# Clock_management.net
KiCad netlist of a schematic drawn in Altium Designer
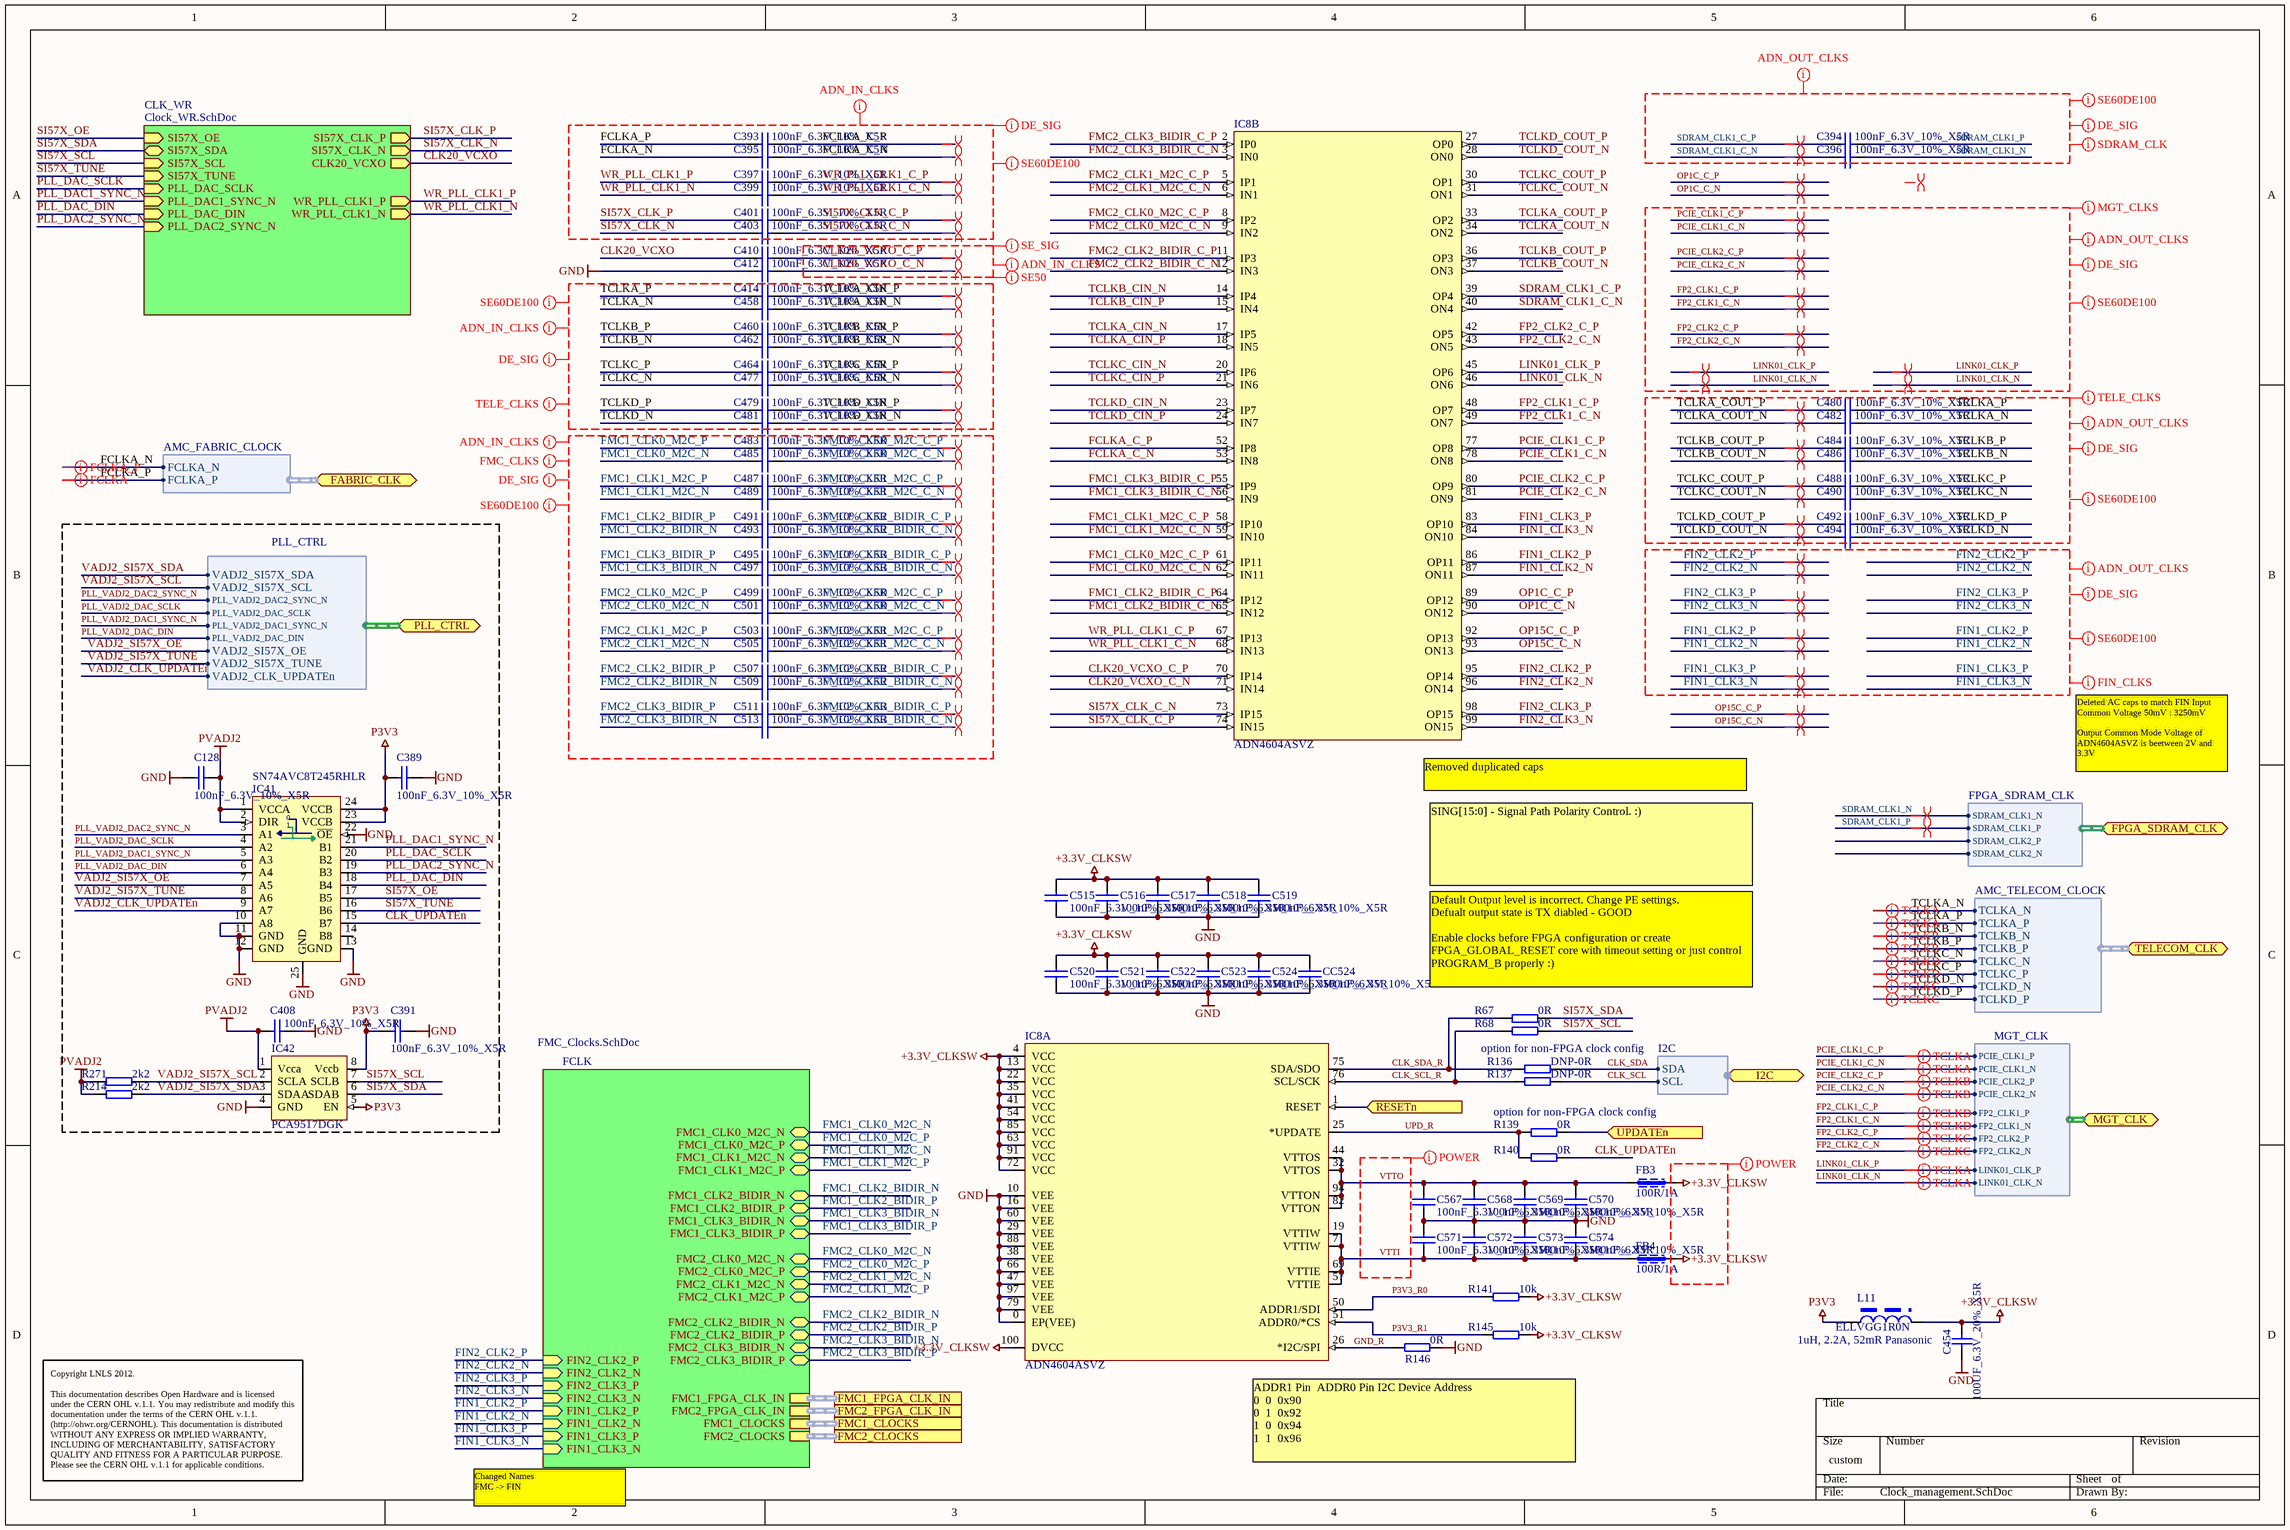
[diagram p0: Clock_management.SchDoc]

(export (version "E")
  (design (tool "Eeschema 10.0.6"))
  (components
    (comp (ref "C128")
      (value "100nF_6.3V_10%_X5R")
      (footprint "0201C")
      (description "Capacitor SMD")
      (libsource (lib "LIBRARY_SCH") (part "CAP_SMD_0201"))
    )
    (comp (ref "C389")
      (value "100nF_6.3V_10%_X5R")
      (footprint "0201C")
      (description "Capacitor SMD")
      (libsource (lib "LIBRARY_SCH") (part "CAP_SMD_0201"))
    )
    (comp (ref "C391")
      (value "100nF_6.3V_10%_X5R")
      (footprint "0201C")
      (description "Capacitor SMD")
      (libsource (lib "LIBRARY_SCH") (part "CAP_SMD_0201"))
    )
    (comp (ref "C393")
      (value "100nF_6.3V_10%_X5R")
      (footprint "0201C")
      (description "Capacitor SMD")
      (libsource (lib "LIBRARY_SCH") (part "CAP_SMD_0201"))
    )
    (comp (ref "C394")
      (value "100nF_6.3V_10%_X5R")
      (footprint "0201C")
      (description "Capacitor SMD")
      (libsource (lib "LIBRARY_SCH") (part "CAP_SMD_0201"))
    )
    (comp (ref "C395")
      (value "100nF_6.3V_10%_X5R")
      (footprint "0201C")
      (description "Capacitor SMD")
      (libsource (lib "LIBRARY_SCH") (part "CAP_SMD_0201"))
    )
    (comp (ref "C396")
      (value "100nF_6.3V_10%_X5R")
      (footprint "0201C")
      (description "Capacitor SMD")
      (libsource (lib "LIBRARY_SCH") (part "CAP_SMD_0201"))
    )
    (comp (ref "C397")
      (value "100nF_6.3V_10%_X5R")
      (footprint "0201C")
      (description "Capacitor SMD")
      (libsource (lib "LIBRARY_SCH") (part "CAP_SMD_0201"))
    )
    (comp (ref "C399")
      (value "100nF_6.3V_10%_X5R")
      (footprint "0201C")
      (description "Capacitor SMD")
      (libsource (lib "LIBRARY_SCH") (part "CAP_SMD_0201"))
    )
    (comp (ref "C401")
      (value "100nF_6.3V_10%_X5R")
      (footprint "0201C")
      (description "Capacitor SMD")
      (libsource (lib "LIBRARY_SCH") (part "CAP_SMD_0201"))
    )
    (comp (ref "C403")
      (value "100nF_6.3V_10%_X5R")
      (footprint "0201C")
      (description "Capacitor SMD")
      (libsource (lib "LIBRARY_SCH") (part "CAP_SMD_0201"))
    )
    (comp (ref "C408")
      (value "100nF_6.3V_10%_X5R")
      (footprint "0201C")
      (description "Capacitor SMD")
      (libsource (lib "LIBRARY_SCH") (part "CAP_SMD_0201"))
    )
    (comp (ref "C410")
      (value "100nF_6.3V_10%_X5R")
      (footprint "0201C")
      (description "Capacitor SMD")
      (libsource (lib "LIBRARY_SCH") (part "CAP_SMD_0201"))
    )
    (comp (ref "C412")
      (value "100nF_6.3V_10%_X5R")
      (footprint "0201C")
      (description "Capacitor SMD")
      (libsource (lib "LIBRARY_SCH") (part "CAP_SMD_0201"))
    )
    (comp (ref "C414")
      (value "100nF_6.3V_10%_X5R")
      (footprint "0201C")
      (description "Capacitor SMD")
      (libsource (lib "LIBRARY_SCH") (part "CAP_SMD_0201"))
    )
    (comp (ref "C454")
      (value "100UF_6.3V_20%_X5R")
      (footprint "CAPC3225X270N")
      (description "Non-polarised capacitor")
      (fields
        (field (name "PART NUMBER") "CC1210_100UF_6.3V_20%_X5R")
        (field (name "VOLTAGE") "6.3V")
        (field (name "AUTHOR") "CERN DEM JLC")
      )
      (libsource (lib "Capacitors") (part "Capacitor - non polarized"))
    )
    (comp (ref "C458")
      (value "100nF_6.3V_10%_X5R")
      (footprint "0201C")
      (description "Capacitor SMD")
      (libsource (lib "LIBRARY_SCH") (part "CAP_SMD_0201"))
    )
    (comp (ref "C460")
      (value "100nF_6.3V_10%_X5R")
      (footprint "0201C")
      (description "Capacitor SMD")
      (libsource (lib "LIBRARY_SCH") (part "CAP_SMD_0201"))
    )
    (comp (ref "C462")
      (value "100nF_6.3V_10%_X5R")
      (footprint "0201C")
      (description "Capacitor SMD")
      (libsource (lib "LIBRARY_SCH") (part "CAP_SMD_0201"))
    )
    (comp (ref "C464")
      (value "100nF_6.3V_10%_X5R")
      (footprint "0201C")
      (description "Capacitor SMD")
      (libsource (lib "LIBRARY_SCH") (part "CAP_SMD_0201"))
    )
    (comp (ref "C477")
      (value "100nF_6.3V_10%_X5R")
      (footprint "0201C")
      (description "Capacitor SMD")
      (libsource (lib "LIBRARY_SCH") (part "CAP_SMD_0201"))
    )
    (comp (ref "C479")
      (value "100nF_6.3V_10%_X5R")
      (footprint "0201C")
      (description "Capacitor SMD")
      (libsource (lib "LIBRARY_SCH") (part "CAP_SMD_0201"))
    )
    (comp (ref "C480")
      (value "100nF_6.3V_10%_X5R")
      (footprint "0201C")
      (description "Capacitor SMD")
      (libsource (lib "LIBRARY_SCH") (part "CAP_SMD_0201"))
    )
    (comp (ref "C481")
      (value "100nF_6.3V_10%_X5R")
      (footprint "0201C")
      (description "Capacitor SMD")
      (libsource (lib "LIBRARY_SCH") (part "CAP_SMD_0201"))
    )
    (comp (ref "C482")
      (value "100nF_6.3V_10%_X5R")
      (footprint "0201C")
      (description "Capacitor SMD")
      (libsource (lib "LIBRARY_SCH") (part "CAP_SMD_0201"))
    )
    (comp (ref "C483")
      (value "100nF_6.3V_10%_X5R")
      (footprint "0201C")
      (description "Capacitor SMD")
      (libsource (lib "LIBRARY_SCH") (part "CAP_SMD_0201"))
    )
    (comp (ref "C484")
      (value "100nF_6.3V_10%_X5R")
      (footprint "0201C")
      (description "Capacitor SMD")
      (libsource (lib "LIBRARY_SCH") (part "CAP_SMD_0201"))
    )
    (comp (ref "C485")
      (value "100nF_6.3V_10%_X5R")
      (footprint "0201C")
      (description "Capacitor SMD")
      (libsource (lib "LIBRARY_SCH") (part "CAP_SMD_0201"))
    )
    (comp (ref "C486")
      (value "100nF_6.3V_10%_X5R")
      (footprint "0201C")
      (description "Capacitor SMD")
      (libsource (lib "LIBRARY_SCH") (part "CAP_SMD_0201"))
    )
    (comp (ref "C487")
      (value "100nF_6.3V_10%_X5R")
      (footprint "0201C")
      (description "Capacitor SMD")
      (libsource (lib "LIBRARY_SCH") (part "CAP_SMD_0201"))
    )
    (comp (ref "C488")
      (value "100nF_6.3V_10%_X5R")
      (footprint "0201C")
      (description "Capacitor SMD")
      (libsource (lib "LIBRARY_SCH") (part "CAP_SMD_0201"))
    )
    (comp (ref "C489")
      (value "100nF_6.3V_10%_X5R")
      (footprint "0201C")
      (description "Capacitor SMD")
      (libsource (lib "LIBRARY_SCH") (part "CAP_SMD_0201"))
    )
    (comp (ref "C490")
      (value "100nF_6.3V_10%_X5R")
      (footprint "0201C")
      (description "Capacitor SMD")
      (libsource (lib "LIBRARY_SCH") (part "CAP_SMD_0201"))
    )
    (comp (ref "C491")
      (value "100nF_6.3V_10%_X5R")
      (footprint "0201C")
      (description "Capacitor SMD")
      (libsource (lib "LIBRARY_SCH") (part "CAP_SMD_0201"))
    )
    (comp (ref "C492")
      (value "100nF_6.3V_10%_X5R")
      (footprint "0201C")
      (description "Capacitor SMD")
      (libsource (lib "LIBRARY_SCH") (part "CAP_SMD_0201"))
    )
    (comp (ref "C493")
      (value "100nF_6.3V_10%_X5R")
      (footprint "0201C")
      (description "Capacitor SMD")
      (libsource (lib "LIBRARY_SCH") (part "CAP_SMD_0201"))
    )
    (comp (ref "C494")
      (value "100nF_6.3V_10%_X5R")
      (footprint "0201C")
      (description "Capacitor SMD")
      (libsource (lib "LIBRARY_SCH") (part "CAP_SMD_0201"))
    )
    (comp (ref "C495")
      (value "100nF_6.3V_10%_X5R")
      (footprint "0201C")
      (description "Capacitor SMD")
      (libsource (lib "LIBRARY_SCH") (part "CAP_SMD_0201"))
    )
    (comp (ref "C497")
      (value "100nF_6.3V_10%_X5R")
      (footprint "0201C")
      (description "Capacitor SMD")
      (libsource (lib "LIBRARY_SCH") (part "CAP_SMD_0201"))
    )
    (comp (ref "C499")
      (value "100nF_6.3V_10%_X5R")
      (footprint "0201C")
      (description "Capacitor SMD")
      (libsource (lib "LIBRARY_SCH") (part "CAP_SMD_0201"))
    )
    (comp (ref "C501")
      (value "100nF_6.3V_10%_X5R")
      (footprint "0201C")
      (description "Capacitor SMD")
      (libsource (lib "LIBRARY_SCH") (part "CAP_SMD_0201"))
    )
    (comp (ref "C503")
      (value "100nF_6.3V_10%_X5R")
      (footprint "0201C")
      (description "Capacitor SMD")
      (libsource (lib "LIBRARY_SCH") (part "CAP_SMD_0201"))
    )
    (comp (ref "C505")
      (value "100nF_6.3V_10%_X5R")
      (footprint "0201C")
      (description "Capacitor SMD")
      (libsource (lib "LIBRARY_SCH") (part "CAP_SMD_0201"))
    )
    (comp (ref "C507")
      (value "100nF_6.3V_10%_X5R")
      (footprint "0201C")
      (description "Capacitor SMD")
      (libsource (lib "LIBRARY_SCH") (part "CAP_SMD_0201"))
    )
    (comp (ref "C509")
      (value "100nF_6.3V_10%_X5R")
      (footprint "0201C")
      (description "Capacitor SMD")
      (libsource (lib "LIBRARY_SCH") (part "CAP_SMD_0201"))
    )
    (comp (ref "C511")
      (value "100nF_6.3V_10%_X5R")
      (footprint "0201C")
      (description "Capacitor SMD")
      (libsource (lib "LIBRARY_SCH") (part "CAP_SMD_0201"))
    )
    (comp (ref "C513")
      (value "100nF_6.3V_10%_X5R")
      (footprint "0201C")
      (description "Capacitor SMD")
      (libsource (lib "LIBRARY_SCH") (part "CAP_SMD_0201"))
    )
    (comp (ref "C515")
      (value "100nF_6.3V_10%_X5R")
      (footprint "0201C")
      (description "Capacitor SMD")
      (libsource (lib "LIBRARY_SCH") (part "CAP_SMD_0201"))
    )
    (comp (ref "C516")
      (value "100nF_6.3V_10%_X5R")
      (footprint "0201C")
      (description "Capacitor SMD")
      (libsource (lib "LIBRARY_SCH") (part "CAP_SMD_0201"))
    )
    (comp (ref "C517")
      (value "100nF_6.3V_10%_X5R")
      (footprint "0201C")
      (description "Capacitor SMD")
      (libsource (lib "LIBRARY_SCH") (part "CAP_SMD_0201"))
    )
    (comp (ref "C518")
      (value "100nF_6.3V_10%_X5R")
      (footprint "0201C")
      (description "Capacitor SMD")
      (libsource (lib "LIBRARY_SCH") (part "CAP_SMD_0201"))
    )
    (comp (ref "C519")
      (value "100nF_6.3V_10%_X5R")
      (footprint "0201C")
      (description "Capacitor SMD")
      (libsource (lib "LIBRARY_SCH") (part "CAP_SMD_0201"))
    )
    (comp (ref "C520")
      (value "100nF_6.3V_10%_X5R")
      (footprint "0201C")
      (description "Capacitor SMD")
      (libsource (lib "LIBRARY_SCH") (part "CAP_SMD_0201"))
    )
    (comp (ref "C521")
      (value "100nF_6.3V_10%_X5R")
      (footprint "0201C")
      (description "Capacitor SMD")
      (libsource (lib "LIBRARY_SCH") (part "CAP_SMD_0201"))
    )
    (comp (ref "C522")
      (value "100nF_6.3V_10%_X5R")
      (footprint "0201C")
      (description "Capacitor SMD")
      (libsource (lib "LIBRARY_SCH") (part "CAP_SMD_0201"))
    )
    (comp (ref "C523")
      (value "100nF_6.3V_10%_X5R")
      (footprint "0201C")
      (description "Capacitor SMD")
      (libsource (lib "LIBRARY_SCH") (part "CAP_SMD_0201"))
    )
    (comp (ref "C524")
      (value "100nF_6.3V_10%_X5R")
      (footprint "0201C")
      (description "Capacitor SMD")
      (libsource (lib "LIBRARY_SCH") (part "CAP_SMD_0201"))
    )
    (comp (ref "C567")
      (value "100nF_6.3V_10%_X5R")
      (footprint "0201C")
      (description "Capacitor SMD")
      (libsource (lib "LIBRARY_SCH") (part "CAP_SMD_0201"))
    )
    (comp (ref "C568")
      (value "100nF_6.3V_10%_X5R")
      (footprint "0201C")
      (description "Capacitor SMD")
      (libsource (lib "LIBRARY_SCH") (part "CAP_SMD_0201"))
    )
    (comp (ref "C569")
      (value "100nF_6.3V_10%_X5R")
      (footprint "0201C")
      (description "Capacitor SMD")
      (libsource (lib "LIBRARY_SCH") (part "CAP_SMD_0201"))
    )
    (comp (ref "C570")
      (value "100nF_6.3V_10%_X5R")
      (footprint "0201C")
      (description "Capacitor SMD")
      (libsource (lib "LIBRARY_SCH") (part "CAP_SMD_0201"))
    )
    (comp (ref "C571")
      (value "100nF_6.3V_10%_X5R")
      (footprint "0201C")
      (description "Capacitor SMD")
      (libsource (lib "LIBRARY_SCH") (part "CAP_SMD_0201"))
    )
    (comp (ref "C572")
      (value "100nF_6.3V_10%_X5R")
      (footprint "0201C")
      (description "Capacitor SMD")
      (libsource (lib "LIBRARY_SCH") (part "CAP_SMD_0201"))
    )
    (comp (ref "C573")
      (value "100nF_6.3V_10%_X5R")
      (footprint "0201C")
      (description "Capacitor SMD")
      (libsource (lib "LIBRARY_SCH") (part "CAP_SMD_0201"))
    )
    (comp (ref "C574")
      (value "100nF_6.3V_10%_X5R")
      (footprint "0201C")
      (description "Capacitor SMD")
      (libsource (lib "LIBRARY_SCH") (part "CAP_SMD_0201"))
    )
    (comp (ref "CC524")
      (value "100nF_6.3V_10%_X5R")
      (footprint "0201C")
      (description "Capacitor SMD")
      (libsource (lib "LIBRARY_SCH") (part "CAP_SMD_0201"))
    )
    (comp (ref "FB3")
      (value "100R/1A")
      (footprint "0603L")
      (description "ferrite bead 100R@100MHz 1A")
      (libsource (lib "LIBRARY_SCH") (part "L_FERRITE_BEAD_0603"))
    )
    (comp (ref "FB4")
      (value "100R/1A")
      (footprint "0603L")
      (description "ferrite bead 100R@100MHz 1A")
      (libsource (lib "LIBRARY_SCH") (part "L_FERRITE_BEAD_0603"))
    )
    (comp (ref "IC8")
      (value "ADN4604ASVZ")
      (footprint "TQFP100_TP")
      (description "16x16 CML crosspoint switch")
      (libsource (lib "LIBRARY_SCH") (part "IFC_ADN4604ASVZ"))
    )
    (comp (ref "IC41")
      (value "SN74AVC8T245RHLR")
      (footprint "QFN50P350X550X100-24N")
      (description "8 channel bidir translator buffer (1.4..3.6V)")
      (libsource (lib "LIBRARY_SCH") (part "74AVC8T245_QFN"))
    )
    (comp (ref "IC42")
      (value "PCA9517DGK")
      (footprint "msop-8")
      (description "LEVEL-TRANSLATING I2C BUS REPEATER")
      (libsource (lib "LIBRARY_SCH") (part "IFC_PCA9517"))
    )
    (comp (ref "L11")
      (value "ELLVGG1R0N")
      (footprint "L_ELLVGG2R2N")
      (description "2.2uH, 1.4A, 92mR Panasonic")
      (fields (field (name "ALTIUM_UNNAMED_1") "1uH, 2.2A, 52mR Panasonic"))
      (libsource (lib "LIBRARY_SCH") (part "L_CHOKE_ELLVGG"))
    )
    (comp (ref "R67")
      (value "0R")
      (footprint "0402R")
      (description "SMD Resistor")
      (libsource (lib "LIBRARY_SCH") (part "RES_0402"))
    )
    (comp (ref "R68")
      (value "0R")
      (footprint "0402R")
      (description "SMD Resistor")
      (libsource (lib "LIBRARY_SCH") (part "RES_0402"))
    )
    (comp (ref "R136")
      (value "DNP-0R")
      (footprint "0402R")
      (description "SMD Resistor")
      (libsource (lib "LIBRARY_SCH") (part "RES_0402"))
    )
    (comp (ref "R137")
      (value "DNP-0R")
      (footprint "0402R")
      (description "SMD Resistor")
      (libsource (lib "LIBRARY_SCH") (part "RES_0402"))
    )
    (comp (ref "R139")
      (value "0R")
      (footprint "0402R")
      (description "SMD Resistor")
      (libsource (lib "LIBRARY_SCH") (part "RES_0402"))
    )
    (comp (ref "R140")
      (value "0R")
      (footprint "0402R")
      (description "SMD Resistor")
      (libsource (lib "LIBRARY_SCH") (part "RES_0402"))
    )
    (comp (ref "R141")
      (value "10k")
      (footprint "0402R")
      (description "SMD Resistor")
      (libsource (lib "LIBRARY_SCH") (part "RES_0402"))
    )
    (comp (ref "R145")
      (value "10k")
      (footprint "0402R")
      (description "SMD Resistor")
      (libsource (lib "LIBRARY_SCH") (part "RES_0402"))
    )
    (comp (ref "R146")
      (value "0R")
      (footprint "0402R")
      (description "SMD Resistor")
      (libsource (lib "LIBRARY_SCH") (part "RES_0402"))
    )
    (comp (ref "R214")
      (value "2k2")
      (footprint "0402R")
      (description "SMD Resistor")
      (libsource (lib "LIBRARY_SCH") (part "RES_0402"))
    )
    (comp (ref "R271")
      (value "2k2")
      (footprint "0402R")
      (description "SMD Resistor")
      (libsource (lib "LIBRARY_SCH") (part "RES_0402"))
    )
  )
  (nets
    (net (code "11") (name "+3.3V_CLKSW") (class "Default")
      (node (ref "C454") (pin "2") (pinfunction "2_2") (pintype "passive"))
      (node (ref "C515") (pin "2") (pinfunction "2_2") (pintype "passive"))
      (node (ref "C516") (pin "2") (pinfunction "2_2") (pintype "passive"))
      (node (ref "C517") (pin "2") (pinfunction "2_2") (pintype "passive"))
      (node (ref "C518") (pin "2") (pinfunction "2_2") (pintype "passive"))
      (node (ref "C519") (pin "2") (pinfunction "2_2") (pintype "passive"))
      (node (ref "C520") (pin "2") (pinfunction "2_2") (pintype "passive"))
      (node (ref "C521") (pin "2") (pinfunction "2_2") (pintype "passive"))
      (node (ref "C522") (pin "2") (pinfunction "2_2") (pintype "passive"))
      (node (ref "C523") (pin "2") (pinfunction "2_2") (pintype "passive"))
      (node (ref "C524") (pin "2") (pinfunction "2_2") (pintype "passive"))
      (node (ref "CC524") (pin "2") (pinfunction "2_2") (pintype "passive"))
      (node (ref "FB3") (pin "2") (pinfunction "2_2") (pintype "passive"))
      (node (ref "FB4") (pin "2") (pinfunction "2_2") (pintype "passive"))
      (node (ref "IC8") (pin "100") (pinfunction "DVCC_100") (pintype "power_in"))
      (node (ref "IC8") (pin "13") (pinfunction "VCC_13") (pintype "power_in"))
      (node (ref "IC8") (pin "22") (pinfunction "VCC_22") (pintype "power_in"))
      (node (ref "IC8") (pin "35") (pinfunction "VCC_35") (pintype "power_in"))
      (node (ref "IC8") (pin "4") (pinfunction "VCC_4") (pintype "power_in"))
      (node (ref "IC8") (pin "41") (pinfunction "VCC_41") (pintype "power_in"))
      (node (ref "IC8") (pin "54") (pinfunction "VCC_54") (pintype "power_in"))
      (node (ref "IC8") (pin "63") (pinfunction "VCC_63") (pintype "power_in"))
      (node (ref "IC8") (pin "72") (pinfunction "VCC_72") (pintype "power_in"))
      (node (ref "IC8") (pin "85") (pinfunction "VCC_85") (pintype "power_in"))
      (node (ref "IC8") (pin "91") (pinfunction "VCC_91") (pintype "power_in"))
      (node (ref "L11") (pin "2") (pintype "passive"))
      (node (ref "R141") (pin "2") (pinfunction "2_2") (pintype "passive"))
      (node (ref "R145") (pin "2") (pinfunction "2_2") (pintype "passive"))
    )
    (net (code "12") (name "/CLK20_VCXO") (class "Default")
      (node (ref "C410") (pin "1") (pinfunction "1_1") (pintype "passive"))
    )
    (net (code "13") (name "/CLK20_VCXO_C_N") (class "Default")
      (node (ref "C412") (pin "2") (pinfunction "2_2") (pintype "passive"))
      (node (ref "IC8") (pin "71") (pinfunction "IN14_71") (pintype "input"))
    )
    (net (code "14") (name "/CLK20_VCXO_C_P") (class "Default")
      (node (ref "C410") (pin "2") (pinfunction "2_2") (pintype "passive"))
      (node (ref "IC8") (pin "70") (pinfunction "IP14_70") (pintype "input"))
    )
    (net (code "15") (name "/CLK_SCL") (class "Default")
      (node (ref "R137") (pin "2") (pinfunction "2_2") (pintype "passive"))
    )
    (net (code "16") (name "/CLK_SCL_R") (class "Default")
      (node (ref "IC8") (pin "76") (pinfunction "SCL/SCK_76") (pintype "input"))
      (node (ref "R137") (pin "1") (pinfunction "1_1") (pintype "passive"))
      (node (ref "R68") (pin "1") (pinfunction "1_1") (pintype "passive"))
    )
    (net (code "17") (name "/CLK_SDA") (class "Default")
      (node (ref "R136") (pin "2") (pinfunction "2_2") (pintype "passive"))
    )
    (net (code "18") (name "/CLK_SDA_R") (class "Default")
      (node (ref "IC8") (pin "75") (pinfunction "SDA/SDO_75") (pintype "bidirectional"))
      (node (ref "R136") (pin "1") (pinfunction "1_1") (pintype "passive"))
      (node (ref "R67") (pin "1") (pinfunction "1_1") (pintype "passive"))
    )
    (net (code "19") (name "/CLK_UPDATEn") (class "Default")
      (node (ref "IC41") (pin "15") (pinfunction "B7_15") (pintype "bidirectional"))
      (node (ref "R140") (pin "2") (pinfunction "2_2") (pintype "passive"))
    )
    (net (code "20") (name "/FCLKA_C_N") (class "Default")
      (node (ref "C395") (pin "2") (pinfunction "2_2") (pintype "passive"))
      (node (ref "IC8") (pin "53") (pinfunction "IN8_53") (pintype "input"))
    )
    (net (code "21") (name "/FCLKA_C_P") (class "Default")
      (node (ref "C393") (pin "2") (pinfunction "2_2") (pintype "passive"))
      (node (ref "IC8") (pin "52") (pinfunction "IP8_52") (pintype "input"))
    )
    (net (code "22") (name "/FCLKA_N") (class "Default")
      (node (ref "C395") (pin "1") (pinfunction "1_1") (pintype "passive"))
    )
    (net (code "23") (name "/FCLKA_P") (class "Default")
      (node (ref "C393") (pin "1") (pinfunction "1_1") (pintype "passive"))
    )
    (net (code "24") (name "/FIN1_CLK2_N") (class "Default")
      (node (ref "IC8") (pin "87") (pinfunction "ON11_87") (pintype "output"))
    )
    (net (code "25") (name "/FIN1_CLK2_P") (class "Default")
      (node (ref "IC8") (pin "86") (pinfunction "OP11_86") (pintype "output"))
    )
    (net (code "26") (name "/FIN1_CLK3_N") (class "Default")
      (node (ref "IC8") (pin "84") (pinfunction "ON10_84") (pintype "output"))
    )
    (net (code "27") (name "/FIN1_CLK3_P") (class "Default")
      (node (ref "IC8") (pin "83") (pinfunction "OP10_83") (pintype "output"))
    )
    (net (code "28") (name "/FIN2_CLK2_N") (class "Default")
      (node (ref "IC8") (pin "96") (pinfunction "ON14_96") (pintype "output"))
    )
    (net (code "29") (name "/FIN2_CLK2_P") (class "Default")
      (node (ref "IC8") (pin "95") (pinfunction "OP14_95") (pintype "output"))
    )
    (net (code "30") (name "/FIN2_CLK3_N") (class "Default")
      (node (ref "IC8") (pin "99") (pinfunction "ON15_99") (pintype "output"))
    )
    (net (code "31") (name "/FIN2_CLK3_P") (class "Default")
      (node (ref "IC8") (pin "98") (pinfunction "OP15_98") (pintype "output"))
    )
    (net (code "32") (name "/FMC1_CLK0_M2C_C_N") (class "Default")
      (node (ref "C485") (pin "2") (pinfunction "2_2") (pintype "passive"))
      (node (ref "IC8") (pin "62") (pinfunction "IN11_62") (pintype "input"))
    )
    (net (code "33") (name "/FMC1_CLK0_M2C_C_P") (class "Default")
      (node (ref "C483") (pin "2") (pinfunction "2_2") (pintype "passive"))
      (node (ref "IC8") (pin "61") (pinfunction "IP11_61") (pintype "input"))
    )
    (net (code "34") (name "/FMC1_CLK0_M2C_N") (class "Default")
      (node (ref "C485") (pin "1") (pinfunction "1_1") (pintype "passive"))
    )
    (net (code "35") (name "/FMC1_CLK0_M2C_P") (class "Default")
      (node (ref "C483") (pin "1") (pinfunction "1_1") (pintype "passive"))
    )
    (net (code "36") (name "/FMC1_CLK1_M2C_C_N") (class "Default")
      (node (ref "C489") (pin "2") (pinfunction "2_2") (pintype "passive"))
      (node (ref "IC8") (pin "59") (pinfunction "IN10_59") (pintype "input"))
    )
    (net (code "37") (name "/FMC1_CLK1_M2C_C_P") (class "Default")
      (node (ref "C487") (pin "2") (pinfunction "2_2") (pintype "passive"))
      (node (ref "IC8") (pin "58") (pinfunction "IP10_58") (pintype "input"))
    )
    (net (code "38") (name "/FMC1_CLK1_M2C_N") (class "Default")
      (node (ref "C489") (pin "1") (pinfunction "1_1") (pintype "passive"))
    )
    (net (code "39") (name "/FMC1_CLK1_M2C_P") (class "Default")
      (node (ref "C487") (pin "1") (pinfunction "1_1") (pintype "passive"))
    )
    (net (code "40") (name "/FMC1_CLK2_BIDIR_C_N") (class "Default")
      (node (ref "C493") (pin "2") (pinfunction "2_2") (pintype "passive"))
      (node (ref "IC8") (pin "65") (pinfunction "IN12_65") (pintype "input"))
    )
    (net (code "41") (name "/FMC1_CLK2_BIDIR_C_P") (class "Default")
      (node (ref "C491") (pin "2") (pinfunction "2_2") (pintype "passive"))
      (node (ref "IC8") (pin "64") (pinfunction "IP12_64") (pintype "input"))
    )
    (net (code "42") (name "/FMC1_CLK2_BIDIR_N") (class "Default")
      (node (ref "C493") (pin "1") (pinfunction "1_1") (pintype "passive"))
    )
    (net (code "43") (name "/FMC1_CLK2_BIDIR_P") (class "Default")
      (node (ref "C491") (pin "1") (pinfunction "1_1") (pintype "passive"))
    )
    (net (code "44") (name "/FMC1_CLK3_BIDIR_C_N") (class "Default")
      (node (ref "C497") (pin "2") (pinfunction "2_2") (pintype "passive"))
      (node (ref "IC8") (pin "56") (pinfunction "IN9_56") (pintype "input"))
    )
    (net (code "45") (name "/FMC1_CLK3_BIDIR_C_P") (class "Default")
      (node (ref "C495") (pin "2") (pinfunction "2_2") (pintype "passive"))
      (node (ref "IC8") (pin "55") (pinfunction "IP9_55") (pintype "input"))
    )
    (net (code "46") (name "/FMC1_CLK3_BIDIR_N") (class "Default")
      (node (ref "C497") (pin "1") (pinfunction "1_1") (pintype "passive"))
    )
    (net (code "47") (name "/FMC1_CLK3_BIDIR_P") (class "Default")
      (node (ref "C495") (pin "1") (pinfunction "1_1") (pintype "passive"))
    )
    (net (code "50") (name "/FMC2_CLK0_M2C_C_N") (class "Default")
      (node (ref "C501") (pin "2") (pinfunction "2_2") (pintype "passive"))
      (node (ref "IC8") (pin "9") (pinfunction "IN2_9") (pintype "input"))
    )
    (net (code "51") (name "/FMC2_CLK0_M2C_C_P") (class "Default")
      (node (ref "C499") (pin "2") (pinfunction "2_2") (pintype "passive"))
      (node (ref "IC8") (pin "8") (pinfunction "IP2_8") (pintype "input"))
    )
    (net (code "52") (name "/FMC2_CLK0_M2C_N") (class "Default")
      (node (ref "C501") (pin "1") (pinfunction "1_1") (pintype "passive"))
    )
    (net (code "53") (name "/FMC2_CLK0_M2C_P") (class "Default")
      (node (ref "C499") (pin "1") (pinfunction "1_1") (pintype "passive"))
    )
    (net (code "54") (name "/FMC2_CLK1_M2C_C_N") (class "Default")
      (node (ref "C505") (pin "2") (pinfunction "2_2") (pintype "passive"))
      (node (ref "IC8") (pin "6") (pinfunction "IN1_6") (pintype "input"))
    )
    (net (code "55") (name "/FMC2_CLK1_M2C_C_P") (class "Default")
      (node (ref "C503") (pin "2") (pinfunction "2_2") (pintype "passive"))
      (node (ref "IC8") (pin "5") (pinfunction "IP1_5") (pintype "input"))
    )
    (net (code "56") (name "/FMC2_CLK1_M2C_N") (class "Default")
      (node (ref "C505") (pin "1") (pinfunction "1_1") (pintype "passive"))
    )
    (net (code "57") (name "/FMC2_CLK1_M2C_P") (class "Default")
      (node (ref "C503") (pin "1") (pinfunction "1_1") (pintype "passive"))
    )
    (net (code "58") (name "/FMC2_CLK2_BIDIR_C_N") (class "Default")
      (node (ref "C509") (pin "2") (pinfunction "2_2") (pintype "passive"))
      (node (ref "IC8") (pin "12") (pinfunction "IN3_12") (pintype "input"))
    )
    (net (code "59") (name "/FMC2_CLK2_BIDIR_C_P") (class "Default")
      (node (ref "C507") (pin "2") (pinfunction "2_2") (pintype "passive"))
      (node (ref "IC8") (pin "11") (pinfunction "IP3_11") (pintype "input"))
    )
    (net (code "60") (name "/FMC2_CLK2_BIDIR_N") (class "Default")
      (node (ref "C509") (pin "1") (pinfunction "1_1") (pintype "passive"))
    )
    (net (code "61") (name "/FMC2_CLK2_BIDIR_P") (class "Default")
      (node (ref "C507") (pin "1") (pinfunction "1_1") (pintype "passive"))
    )
    (net (code "62") (name "/FMC2_CLK3_BIDIR_C_N") (class "Default")
      (node (ref "C513") (pin "2") (pinfunction "2_2") (pintype "passive"))
      (node (ref "IC8") (pin "3") (pinfunction "IN0_3") (pintype "input"))
    )
    (net (code "63") (name "/FMC2_CLK3_BIDIR_C_P") (class "Default")
      (node (ref "C511") (pin "2") (pinfunction "2_2") (pintype "passive"))
      (node (ref "IC8") (pin "2") (pinfunction "IP0_2") (pintype "input"))
    )
    (net (code "64") (name "/FMC2_CLK3_BIDIR_N") (class "Default")
      (node (ref "C513") (pin "1") (pinfunction "1_1") (pintype "passive"))
    )
    (net (code "65") (name "/FMC2_CLK3_BIDIR_P") (class "Default")
      (node (ref "C511") (pin "1") (pinfunction "1_1") (pintype "passive"))
    )
    (net (code "68") (name "/FP2_CLK1_C_N") (class "Default")
      (node (ref "IC8") (pin "49") (pinfunction "ON7_49") (pintype "output"))
    )
    (net (code "69") (name "/FP2_CLK1_C_P") (class "Default")
      (node (ref "IC8") (pin "48") (pinfunction "OP7_48") (pintype "output"))
    )
    (net (code "70") (name "/FP2_CLK2_C_N") (class "Default")
      (node (ref "IC8") (pin "43") (pinfunction "ON5_43") (pintype "output"))
    )
    (net (code "71") (name "/FP2_CLK2_C_P") (class "Default")
      (node (ref "IC8") (pin "42") (pinfunction "OP5_42") (pintype "output"))
    )
    (net (code "72") (name "/GND_R") (class "Default")
      (node (ref "IC8") (pin "26") (pinfunction "*I2C/SPI_26") (pintype "input"))
      (node (ref "R146") (pin "1") (pinfunction "1_1") (pintype "passive"))
    )
    (net (code "73") (name "/LINK01_CLK_N") (class "Default")
      (node (ref "IC8") (pin "46") (pinfunction "ON6_46") (pintype "output"))
    )
    (net (code "74") (name "/LINK01_CLK_P") (class "Default")
      (node (ref "IC8") (pin "45") (pinfunction "OP6_45") (pintype "output"))
    )
    (net (code "75") (name "/OP1C_C_N") (class "Default")
      (node (ref "IC8") (pin "90") (pinfunction "ON12_90") (pintype "output"))
    )
    (net (code "76") (name "/OP1C_C_P") (class "Default")
      (node (ref "IC8") (pin "89") (pinfunction "OP12_89") (pintype "output"))
    )
    (net (code "77") (name "/OP15C_C_N") (class "Default")
      (node (ref "IC8") (pin "93") (pinfunction "ON13_93") (pintype "output"))
    )
    (net (code "78") (name "/OP15C_C_P") (class "Default")
      (node (ref "IC8") (pin "92") (pinfunction "OP13_92") (pintype "output"))
    )
    (net (code "79") (name "/P3V3_R0") (class "Default")
      (node (ref "IC8") (pin "50") (pinfunction "ADDR1/SDI_50") (pintype "input"))
      (node (ref "R141") (pin "1") (pinfunction "1_1") (pintype "passive"))
    )
    (net (code "80") (name "/P3V3_R1") (class "Default")
      (node (ref "IC8") (pin "51") (pinfunction "ADDR0/*CS_51") (pintype "input"))
      (node (ref "R145") (pin "1") (pinfunction "1_1") (pintype "passive"))
    )
    (net (code "81") (name "/PCIE_CLK1_C_N") (class "Default")
      (node (ref "IC8") (pin "78") (pinfunction "ON8_78") (pintype "output"))
    )
    (net (code "82") (name "/PCIE_CLK1_C_P") (class "Default")
      (node (ref "IC8") (pin "77") (pinfunction "OP8_77") (pintype "output"))
    )
    (net (code "83") (name "/PCIE_CLK2_C_N") (class "Default")
      (node (ref "IC8") (pin "81") (pinfunction "ON9_81") (pintype "output"))
    )
    (net (code "84") (name "/PCIE_CLK2_C_P") (class "Default")
      (node (ref "IC8") (pin "80") (pinfunction "OP9_80") (pintype "output"))
    )
    (net (code "85") (name "/PLL_DAC1_SYNC_N") (class "Default")
      (node (ref "IC41") (pin "21") (pinfunction "B1_21") (pintype "bidirectional"))
    )
    (net (code "86") (name "/PLL_DAC2_SYNC_N") (class "Default")
      (node (ref "IC41") (pin "19") (pinfunction "B3_19") (pintype "bidirectional"))
    )
    (net (code "87") (name "/PLL_DAC_DIN") (class "Default")
      (node (ref "IC41") (pin "18") (pinfunction "B4_18") (pintype "bidirectional"))
    )
    (net (code "88") (name "/PLL_DAC_SCLK") (class "Default")
      (node (ref "IC41") (pin "20") (pinfunction "B2_20") (pintype "bidirectional"))
    )
    (net (code "89") (name "/PLL_VADJ2_DAC1_SYNC_N") (class "Default")
      (node (ref "IC41") (pin "5") (pinfunction "A3_5") (pintype "bidirectional"))
    )
    (net (code "90") (name "/PLL_VADJ2_DAC2_SYNC_N") (class "Default")
      (node (ref "IC41") (pin "3") (pinfunction "A1_3") (pintype "bidirectional"))
    )
    (net (code "91") (name "/PLL_VADJ2_DAC_DIN") (class "Default")
      (node (ref "IC41") (pin "6") (pinfunction "A4_6") (pintype "bidirectional"))
    )
    (net (code "92") (name "/PLL_VADJ2_DAC_SCLK") (class "Default")
      (node (ref "IC41") (pin "4") (pinfunction "A2_4") (pintype "bidirectional"))
    )
    (net (code "93") (name "/RESETn") (class "Default")
      (node (ref "IC8") (pin "1") (pinfunction "RESET_1") (pintype "input"))
    )
    (net (code "94") (name "/SDRAM_CLK1_C_N") (class "Default")
      (node (ref "C396") (pin "1") (pinfunction "1_1") (pintype "passive"))
      (node (ref "IC8") (pin "40") (pinfunction "ON4_40") (pintype "output"))
    )
    (net (code "95") (name "/SDRAM_CLK1_C_P") (class "Default")
      (node (ref "C394") (pin "1") (pinfunction "1_1") (pintype "passive"))
      (node (ref "IC8") (pin "39") (pinfunction "OP4_39") (pintype "output"))
    )
    (net (code "96") (name "/SDRAM_CLK1_N") (class "Default")
      (node (ref "C396") (pin "2") (pinfunction "2_2") (pintype "passive"))
    )
    (net (code "97") (name "/SDRAM_CLK1_P") (class "Default")
      (node (ref "C394") (pin "2") (pinfunction "2_2") (pintype "passive"))
    )
    (net (code "98") (name "/SI57X_CLK_C_N") (class "Default")
      (node (ref "C403") (pin "2") (pinfunction "2_2") (pintype "passive"))
      (node (ref "IC8") (pin "73") (pinfunction "IP15_73") (pintype "input"))
    )
    (net (code "99") (name "/SI57X_CLK_C_P") (class "Default")
      (node (ref "C401") (pin "2") (pinfunction "2_2") (pintype "passive"))
      (node (ref "IC8") (pin "74") (pinfunction "IN15_74") (pintype "input"))
    )
    (net (code "100") (name "/SI57X_CLK_N") (class "Default")
      (node (ref "C403") (pin "1") (pinfunction "1_1") (pintype "passive"))
    )
    (net (code "101") (name "/SI57X_CLK_P") (class "Default")
      (node (ref "C401") (pin "1") (pinfunction "1_1") (pintype "passive"))
    )
    (net (code "102") (name "/SI57X_OE") (class "Default")
      (node (ref "IC41") (pin "17") (pinfunction "B5_17") (pintype "bidirectional"))
    )
    (net (code "103") (name "/SI57X_SCL") (class "Default")
      (node (ref "IC42") (pin "7") (pinfunction "SCLB_7") (pintype "bidirectional"))
      (node (ref "R68") (pin "2") (pinfunction "2_2") (pintype "passive"))
    )
    (net (code "104") (name "/SI57X_SDA") (class "Default")
      (node (ref "IC42") (pin "6") (pinfunction "SDAB_6") (pintype "bidirectional"))
      (node (ref "R67") (pin "2") (pinfunction "2_2") (pintype "passive"))
    )
    (net (code "105") (name "/SI57X_TUNE") (class "Default")
      (node (ref "IC41") (pin "16") (pinfunction "B6_16") (pintype "bidirectional"))
    )
    (net (code "106") (name "/TCLKA_CIN_N") (class "Default")
      (node (ref "C458") (pin "2") (pinfunction "2_2") (pintype "passive"))
      (node (ref "IC8") (pin "17") (pinfunction "IP5_17") (pintype "input"))
    )
    (net (code "107") (name "/TCLKA_CIN_P") (class "Default")
      (node (ref "C414") (pin "2") (pinfunction "2_2") (pintype "passive"))
      (node (ref "IC8") (pin "18") (pinfunction "IN5_18") (pintype "input"))
    )
    (net (code "108") (name "/TCLKA_COUT_N") (class "Default")
      (node (ref "C482") (pin "1") (pinfunction "1_1") (pintype "passive"))
      (node (ref "IC8") (pin "34") (pinfunction "ON2_34") (pintype "output"))
    )
    (net (code "109") (name "/TCLKA_COUT_P") (class "Default")
      (node (ref "C480") (pin "1") (pinfunction "1_1") (pintype "passive"))
      (node (ref "IC8") (pin "33") (pinfunction "OP2_33") (pintype "output"))
    )
    (net (code "110") (name "/TCLKA_N") (class "Default")
      (node (ref "C458") (pin "1") (pinfunction "1_1") (pintype "passive"))
      (node (ref "C482") (pin "2") (pinfunction "2_2") (pintype "passive"))
    )
    (net (code "111") (name "/TCLKA_P") (class "Default")
      (node (ref "C414") (pin "1") (pinfunction "1_1") (pintype "passive"))
      (node (ref "C480") (pin "2") (pinfunction "2_2") (pintype "passive"))
    )
    (net (code "112") (name "/TCLKB_CIN_N") (class "Default")
      (node (ref "C462") (pin "2") (pinfunction "2_2") (pintype "passive"))
      (node (ref "IC8") (pin "14") (pinfunction "IP4_14") (pintype "input"))
    )
    (net (code "113") (name "/TCLKB_CIN_P") (class "Default")
      (node (ref "C460") (pin "2") (pinfunction "2_2") (pintype "passive"))
      (node (ref "IC8") (pin "15") (pinfunction "IN4_15") (pintype "input"))
    )
    (net (code "114") (name "/TCLKB_COUT_N") (class "Default")
      (node (ref "C486") (pin "1") (pinfunction "1_1") (pintype "passive"))
      (node (ref "IC8") (pin "37") (pinfunction "ON3_37") (pintype "output"))
    )
    (net (code "115") (name "/TCLKB_COUT_P") (class "Default")
      (node (ref "C484") (pin "1") (pinfunction "1_1") (pintype "passive"))
      (node (ref "IC8") (pin "36") (pinfunction "OP3_36") (pintype "output"))
    )
    (net (code "116") (name "/TCLKB_N") (class "Default")
      (node (ref "C462") (pin "1") (pinfunction "1_1") (pintype "passive"))
      (node (ref "C486") (pin "2") (pinfunction "2_2") (pintype "passive"))
    )
    (net (code "117") (name "/TCLKB_P") (class "Default")
      (node (ref "C460") (pin "1") (pinfunction "1_1") (pintype "passive"))
      (node (ref "C484") (pin "2") (pinfunction "2_2") (pintype "passive"))
    )
    (net (code "118") (name "/TCLKC_CIN_N") (class "Default")
      (node (ref "C477") (pin "2") (pinfunction "2_2") (pintype "passive"))
      (node (ref "IC8") (pin "20") (pinfunction "IP6_20") (pintype "input"))
    )
    (net (code "119") (name "/TCLKC_CIN_P") (class "Default")
      (node (ref "C464") (pin "2") (pinfunction "2_2") (pintype "passive"))
      (node (ref "IC8") (pin "21") (pinfunction "IN6_21") (pintype "input"))
    )
    (net (code "120") (name "/TCLKC_COUT_N") (class "Default")
      (node (ref "C490") (pin "1") (pinfunction "1_1") (pintype "passive"))
      (node (ref "IC8") (pin "31") (pinfunction "ON1_31") (pintype "output"))
    )
    (net (code "121") (name "/TCLKC_COUT_P") (class "Default")
      (node (ref "C488") (pin "1") (pinfunction "1_1") (pintype "passive"))
      (node (ref "IC8") (pin "30") (pinfunction "OP1_30") (pintype "output"))
    )
    (net (code "122") (name "/TCLKC_N") (class "Default")
      (node (ref "C477") (pin "1") (pinfunction "1_1") (pintype "passive"))
      (node (ref "C490") (pin "2") (pinfunction "2_2") (pintype "passive"))
    )
    (net (code "123") (name "/TCLKC_P") (class "Default")
      (node (ref "C464") (pin "1") (pinfunction "1_1") (pintype "passive"))
      (node (ref "C488") (pin "2") (pinfunction "2_2") (pintype "passive"))
    )
    (net (code "124") (name "/TCLKD_CIN_N") (class "Default")
      (node (ref "C481") (pin "2") (pinfunction "2_2") (pintype "passive"))
      (node (ref "IC8") (pin "23") (pinfunction "IP7_23") (pintype "input"))
    )
    (net (code "125") (name "/TCLKD_CIN_P") (class "Default")
      (node (ref "C479") (pin "2") (pinfunction "2_2") (pintype "passive"))
      (node (ref "IC8") (pin "24") (pinfunction "IN7_24") (pintype "input"))
    )
    (net (code "126") (name "/TCLKD_COUT_N") (class "Default")
      (node (ref "C494") (pin "1") (pinfunction "1_1") (pintype "passive"))
      (node (ref "IC8") (pin "28") (pinfunction "ON0_28") (pintype "output"))
    )
    (net (code "127") (name "/TCLKD_COUT_P") (class "Default")
      (node (ref "C492") (pin "1") (pinfunction "1_1") (pintype "passive"))
      (node (ref "IC8") (pin "27") (pinfunction "OP0_27") (pintype "output"))
    )
    (net (code "128") (name "/TCLKD_N") (class "Default")
      (node (ref "C481") (pin "1") (pinfunction "1_1") (pintype "passive"))
      (node (ref "C494") (pin "2") (pinfunction "2_2") (pintype "passive"))
    )
    (net (code "129") (name "/TCLKD_P") (class "Default")
      (node (ref "C479") (pin "1") (pinfunction "1_1") (pintype "passive"))
      (node (ref "C492") (pin "2") (pinfunction "2_2") (pintype "passive"))
    )
    (net (code "130") (name "/UPDATEn") (class "Default")
      (node (ref "R139") (pin "2") (pinfunction "2_2") (pintype "passive"))
    )
    (net (code "131") (name "/UPD_R") (class "Default")
      (node (ref "IC8") (pin "25") (pinfunction "*UPDATE_25") (pintype "passive"))
      (node (ref "R139") (pin "1") (pinfunction "1_1") (pintype "passive"))
      (node (ref "R140") (pin "1") (pinfunction "1_1") (pintype "passive"))
    )
    (net (code "132") (name "/VADJ2_CLK_UPDATEn") (class "Default")
      (node (ref "IC41") (pin "9") (pinfunction "A7_9") (pintype "bidirectional"))
    )
    (net (code "133") (name "/VADJ2_SI57X_OE") (class "Default")
      (node (ref "IC41") (pin "7") (pinfunction "A5_7") (pintype "bidirectional"))
    )
    (net (code "134") (name "/VADJ2_SI57X_SCL") (class "Default")
      (node (ref "IC42") (pin "2") (pinfunction "SCLA_2") (pintype "bidirectional"))
      (node (ref "R271") (pin "2") (pinfunction "2_2") (pintype "passive"))
    )
    (net (code "135") (name "/VADJ2_SI57X_SDA") (class "Default")
      (node (ref "IC42") (pin "3") (pinfunction "SDAA_3") (pintype "bidirectional"))
      (node (ref "R214") (pin "2") (pinfunction "2_2") (pintype "passive"))
    )
    (net (code "136") (name "/VADJ2_SI57X_TUNE") (class "Default")
      (node (ref "IC41") (pin "8") (pinfunction "A6_8") (pintype "bidirectional"))
    )
    (net (code "137") (name "/VTTI") (class "Default")
      (node (ref "C571") (pin "1") (pinfunction "1_1") (pintype "passive"))
      (node (ref "C572") (pin "1") (pinfunction "1_1") (pintype "passive"))
      (node (ref "C573") (pin "1") (pinfunction "1_1") (pintype "passive"))
      (node (ref "C574") (pin "1") (pinfunction "1_1") (pintype "passive"))
      (node (ref "FB4") (pin "1") (pinfunction "1_1") (pintype "passive"))
      (node (ref "IC8") (pin "19") (pinfunction "VTTIW_19") (pintype "passive"))
      (node (ref "IC8") (pin "57") (pinfunction "VTTIE_57") (pintype "passive"))
      (node (ref "IC8") (pin "69") (pinfunction "VTTIE_69") (pintype "passive"))
      (node (ref "IC8") (pin "7") (pinfunction "VTTIW_7") (pintype "passive"))
    )
    (net (code "138") (name "/VTTO") (class "Default")
      (node (ref "C567") (pin "2") (pinfunction "2_2") (pintype "passive"))
      (node (ref "C568") (pin "2") (pinfunction "2_2") (pintype "passive"))
      (node (ref "C569") (pin "2") (pinfunction "2_2") (pintype "passive"))
      (node (ref "C570") (pin "2") (pinfunction "2_2") (pintype "passive"))
      (node (ref "FB3") (pin "1") (pinfunction "1_1") (pintype "passive"))
      (node (ref "IC8") (pin "32") (pinfunction "VTTOS_32") (pintype "passive"))
      (node (ref "IC8") (pin "44") (pinfunction "VTTOS_44") (pintype "passive"))
      (node (ref "IC8") (pin "82") (pinfunction "VTTON_82") (pintype "passive"))
      (node (ref "IC8") (pin "94") (pinfunction "VTTON_94") (pintype "passive"))
    )
    (net (code "139") (name "/WR_PLL_CLK1_C_N") (class "Default")
      (node (ref "C399") (pin "2") (pinfunction "2_2") (pintype "passive"))
      (node (ref "IC8") (pin "68") (pinfunction "IN13_68") (pintype "input"))
    )
    (net (code "140") (name "/WR_PLL_CLK1_C_P") (class "Default")
      (node (ref "C397") (pin "2") (pinfunction "2_2") (pintype "passive"))
      (node (ref "IC8") (pin "67") (pinfunction "IP13_67") (pintype "input"))
    )
    (net (code "141") (name "/WR_PLL_CLK1_N") (class "Default")
      (node (ref "C399") (pin "1") (pinfunction "1_1") (pintype "passive"))
    )
    (net (code "142") (name "/WR_PLL_CLK1_P") (class "Default")
      (node (ref "C397") (pin "1") (pinfunction "1_1") (pintype "passive"))
    )
    (net (code "149") (name "GND") (class "Default")
      (node (ref "C128") (pin "1") (pinfunction "1_1") (pintype "passive"))
      (node (ref "C389") (pin "1") (pinfunction "1_1") (pintype "passive"))
      (node (ref "C391") (pin "1") (pinfunction "1_1") (pintype "passive"))
      (node (ref "C408") (pin "1") (pinfunction "1_1") (pintype "passive"))
      (node (ref "C412") (pin "1") (pinfunction "1_1") (pintype "passive"))
      (node (ref "C454") (pin "1") (pinfunction "1_1") (pintype "passive"))
      (node (ref "C515") (pin "1") (pinfunction "1_1") (pintype "passive"))
      (node (ref "C516") (pin "1") (pinfunction "1_1") (pintype "passive"))
      (node (ref "C517") (pin "1") (pinfunction "1_1") (pintype "passive"))
      (node (ref "C518") (pin "1") (pinfunction "1_1") (pintype "passive"))
      (node (ref "C519") (pin "1") (pinfunction "1_1") (pintype "passive"))
      (node (ref "C520") (pin "1") (pinfunction "1_1") (pintype "passive"))
      (node (ref "C521") (pin "1") (pinfunction "1_1") (pintype "passive"))
      (node (ref "C522") (pin "1") (pinfunction "1_1") (pintype "passive"))
      (node (ref "C523") (pin "1") (pinfunction "1_1") (pintype "passive"))
      (node (ref "C524") (pin "1") (pinfunction "1_1") (pintype "passive"))
      (node (ref "C567") (pin "1") (pinfunction "1_1") (pintype "passive"))
      (node (ref "C568") (pin "1") (pinfunction "1_1") (pintype "passive"))
      (node (ref "C569") (pin "1") (pinfunction "1_1") (pintype "passive"))
      (node (ref "C570") (pin "1") (pinfunction "1_1") (pintype "passive"))
      (node (ref "C571") (pin "2") (pinfunction "2_2") (pintype "passive"))
      (node (ref "C572") (pin "2") (pinfunction "2_2") (pintype "passive"))
      (node (ref "C573") (pin "2") (pinfunction "2_2") (pintype "passive"))
      (node (ref "C574") (pin "2") (pinfunction "2_2") (pintype "passive"))
      (node (ref "CC524") (pin "1") (pinfunction "1_1") (pintype "passive"))
      (node (ref "IC41") (pin "10") (pinfunction "A8_10") (pintype "bidirectional"))
      (node (ref "IC41") (pin "11") (pinfunction "GND_11") (pintype "power_in"))
      (node (ref "IC41") (pin "12") (pinfunction "GND_12") (pintype "power_in"))
      (node (ref "IC41") (pin "13") (pinfunction "GND_13") (pintype "power_in"))
      (node (ref "IC41") (pin "22") (pinfunction "~{OE}_22") (pintype "input"))
      (node (ref "IC41") (pin "25") (pinfunction "GND_25") (pintype "power_in"))
      (node (ref "IC42") (pin "4") (pinfunction "GND_4") (pintype "power_in"))
      (node (ref "IC8") (pin "0") (pinfunction "EP(VEE)_0") (pintype "power_in"))
      (node (ref "IC8") (pin "10") (pinfunction "VEE_10") (pintype "power_in"))
      (node (ref "IC8") (pin "16") (pinfunction "VEE_16") (pintype "power_in"))
      (node (ref "IC8") (pin "29") (pinfunction "VEE_29") (pintype "power_in"))
      (node (ref "IC8") (pin "38") (pinfunction "VEE_38") (pintype "power_in"))
      (node (ref "IC8") (pin "47") (pinfunction "VEE_47") (pintype "power_in"))
      (node (ref "IC8") (pin "60") (pinfunction "VEE_60") (pintype "power_in"))
      (node (ref "IC8") (pin "66") (pinfunction "VEE_66") (pintype "power_in"))
      (node (ref "IC8") (pin "79") (pinfunction "VEE_79") (pintype "power_in"))
      (node (ref "IC8") (pin "88") (pinfunction "VEE_88") (pintype "power_in"))
      (node (ref "IC8") (pin "97") (pinfunction "VEE_97") (pintype "power_in"))
      (node (ref "R146") (pin "2") (pinfunction "2_2") (pintype "passive"))
    )
    (net (code "150") (name "P3V3") (class "Default")
      (node (ref "C389") (pin "2") (pinfunction "2_2") (pintype "passive"))
      (node (ref "C391") (pin "2") (pinfunction "2_2") (pintype "passive"))
      (node (ref "IC41") (pin "23") (pinfunction "VCCB_23") (pintype "power_in"))
      (node (ref "IC41") (pin "24") (pinfunction "VCCB_24") (pintype "power_in"))
      (node (ref "IC42") (pin "5") (pinfunction "EN_5") (pintype "input"))
      (node (ref "IC42") (pin "8") (pinfunction "Vccb_8") (pintype "power_in"))
      (node (ref "L11") (pin "1") (pintype "passive"))
    )
    (net (code "151") (name "PVADJ2") (class "Default")
      (node (ref "C128") (pin "2") (pinfunction "2_2") (pintype "passive"))
      (node (ref "C408") (pin "2") (pinfunction "2_2") (pintype "passive"))
      (node (ref "IC41") (pin "1") (pinfunction "VCCA_1") (pintype "power_in"))
      (node (ref "IC41") (pin "2") (pinfunction "DIR_2") (pintype "input"))
      (node (ref "IC42") (pin "1") (pinfunction "Vcca_1") (pintype "power_in"))
      (node (ref "R214") (pin "1") (pinfunction "1_1") (pintype "passive"))
      (node (ref "R271") (pin "1") (pinfunction "1_1") (pintype "passive"))
    )
    (net (code "152") (name "unconnected-(IC41-B8-Pad14)") (class "Default")
      (node (ref "IC41") (pin "14") (pinfunction "B8_14") (pintype "bidirectional"))
    )
  )
)
